# kill-switches_schematic.net
KiCad netlist of a schematic drawn in Altium Designer
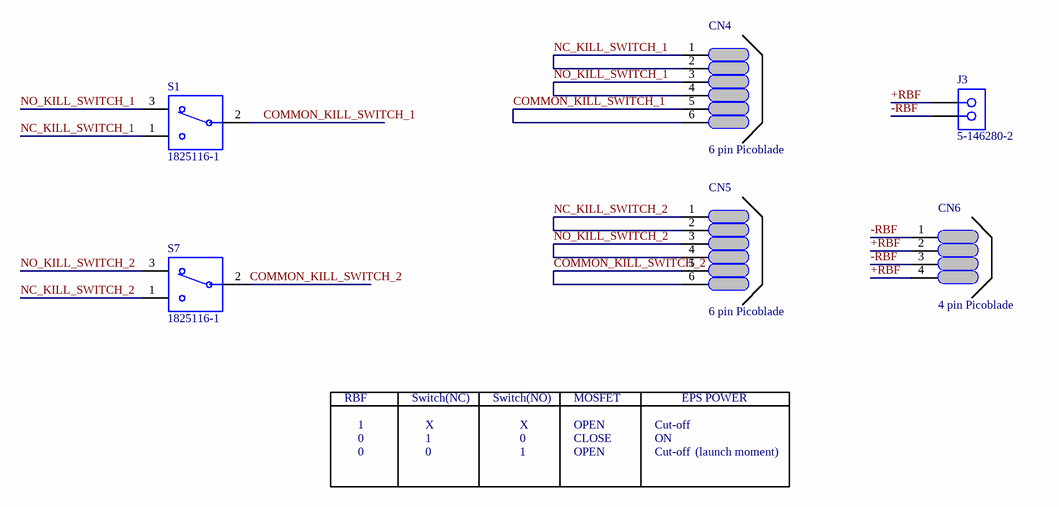
[diagram p0: kill-switches_schematic.SchDoc]

(export (version "E")
  (design (tool "Eeschema 10.0.6"))
  (components
    (comp (ref "CN4")
      (value "6 pin Picoblade")
      (footprint "PICO BLADE 0533980671")
      (description "1.25mm Pitch PicoBlade™ Header, Surface Mount, Vertical, 6 Circuits")
      (fields (field (name "MANUFACTURER") "Molex") (field (name "MANUFACTURER PART NUMBER") "53398-0671"))
      (libsource (lib "flatsat_platform_2") (part "53398-0671"))
    )
    (comp (ref "CN5")
      (value "6 pin Picoblade")
      (footprint "PICO BLADE 0533980671")
      (description "1.25mm Pitch PicoBlade™ Header, Surface Mount, Vertical, 6 Circuits")
      (fields (field (name "MANUFACTURER") "Molex") (field (name "MANUFACTURER PART NUMBER") "53398-0671"))
      (libsource (lib "flatsat_platform_2") (part "53398-0671"))
    )
    (comp (ref "CN6")
      (value "4 pin Picoblade")
      (footprint "PICO BLADE 0533980471")
      (description "1.25mm Pitch PicoBlade™ Header, Surface Mount, Vertical, 4 Circuits")
      (fields (field (name "MANUFACTURER") "Molex") (field (name "MANUFACTURER PART NUMBER") "53398-0471"))
      (libsource (lib "flatsat_platform_2") (part "0533980471"))
    )
    (comp (ref "J3")
      (value "5-146280-2")
      (footprint "PIN BAR 2 2.54mm 180 GRAUS")
      (description "02 MODII HDR SRST B/A .100CL")
      (fields (field (name "MF") "TE Connectivity"))
      (libsource (lib "flatsat_platform_2") (part "5-146280-2"))
    )
    (comp (ref "S1")
      (value "1825116-1")
      (footprint "SW_1825116-1")
      (description "Slide Switch SPDT Through Hole, Right Angle")
      (fields (field (name "MF") "TE Connectivity"))
      (libsource (lib "flatsat_platform_2") (part "1825116-1"))
    )
    (comp (ref "S7")
      (value "1825116-1")
      (footprint "SW_1825116-1")
      (description "Slide Switch SPDT Through Hole, Right Angle")
      (fields (field (name "MF") "TE Connectivity"))
      (libsource (lib "flatsat_platform_2") (part "1825116-1"))
    )
  )
  (nets
    (net (code "1") (name "/+RBF") (class "Default")
      (node (ref "CN6") (pin "2") (pinfunction "2_2") (pintype "passive"))
      (node (ref "CN6") (pin "4") (pinfunction "4_4") (pintype "passive"))
      (node (ref "J3") (pin "1") (pinfunction "1_1") (pintype "passive"))
    )
    (net (code "2") (name "/-RBF") (class "Default")
      (node (ref "CN6") (pin "1") (pinfunction "1_1") (pintype "passive"))
      (node (ref "CN6") (pin "3") (pinfunction "3_3") (pintype "passive"))
      (node (ref "J3") (pin "2") (pinfunction "2_2") (pintype "passive"))
    )
    (net (code "3") (name "/COMMON_KILL_SWITCH_1") (class "Default")
      (node (ref "CN4") (pin "5") (pinfunction "5_5") (pintype "passive"))
      (node (ref "CN4") (pin "6") (pinfunction "6_6") (pintype "passive"))
      (node (ref "S1") (pin "2") (pinfunction "2_2") (pintype "passive"))
    )
    (net (code "4") (name "/COMMON_KILL_SWITCH_2") (class "Default")
      (node (ref "CN5") (pin "5") (pinfunction "5_5") (pintype "passive"))
      (node (ref "CN5") (pin "6") (pinfunction "6_6") (pintype "passive"))
      (node (ref "S7") (pin "2") (pinfunction "2_2") (pintype "passive"))
    )
    (net (code "5") (name "/NC_KILL_SWITCH_1") (class "Default")
      (node (ref "CN4") (pin "1") (pinfunction "1_1") (pintype "passive"))
      (node (ref "CN4") (pin "2") (pinfunction "2_2") (pintype "passive"))
      (node (ref "S1") (pin "1") (pinfunction "1_1") (pintype "passive"))
    )
    (net (code "6") (name "/NC_KILL_SWITCH_2") (class "Default")
      (node (ref "CN5") (pin "1") (pinfunction "1_1") (pintype "passive"))
      (node (ref "CN5") (pin "2") (pinfunction "2_2") (pintype "passive"))
      (node (ref "S7") (pin "1") (pinfunction "1_1") (pintype "passive"))
    )
    (net (code "7") (name "/NO_KILL_SWITCH_1") (class "Default")
      (node (ref "CN4") (pin "3") (pinfunction "3_3") (pintype "passive"))
      (node (ref "CN4") (pin "4") (pinfunction "4_4") (pintype "passive"))
      (node (ref "S1") (pin "3") (pinfunction "3_3") (pintype "passive"))
    )
    (net (code "8") (name "/NO_KILL_SWITCH_2") (class "Default")
      (node (ref "CN5") (pin "3") (pinfunction "3_3") (pintype "passive"))
      (node (ref "CN5") (pin "4") (pinfunction "4_4") (pintype "passive"))
      (node (ref "S7") (pin "3") (pinfunction "3_3") (pintype "passive"))
    )
  )
)
